# MCU.net
KiCad netlist of a schematic drawn in Altium Designer
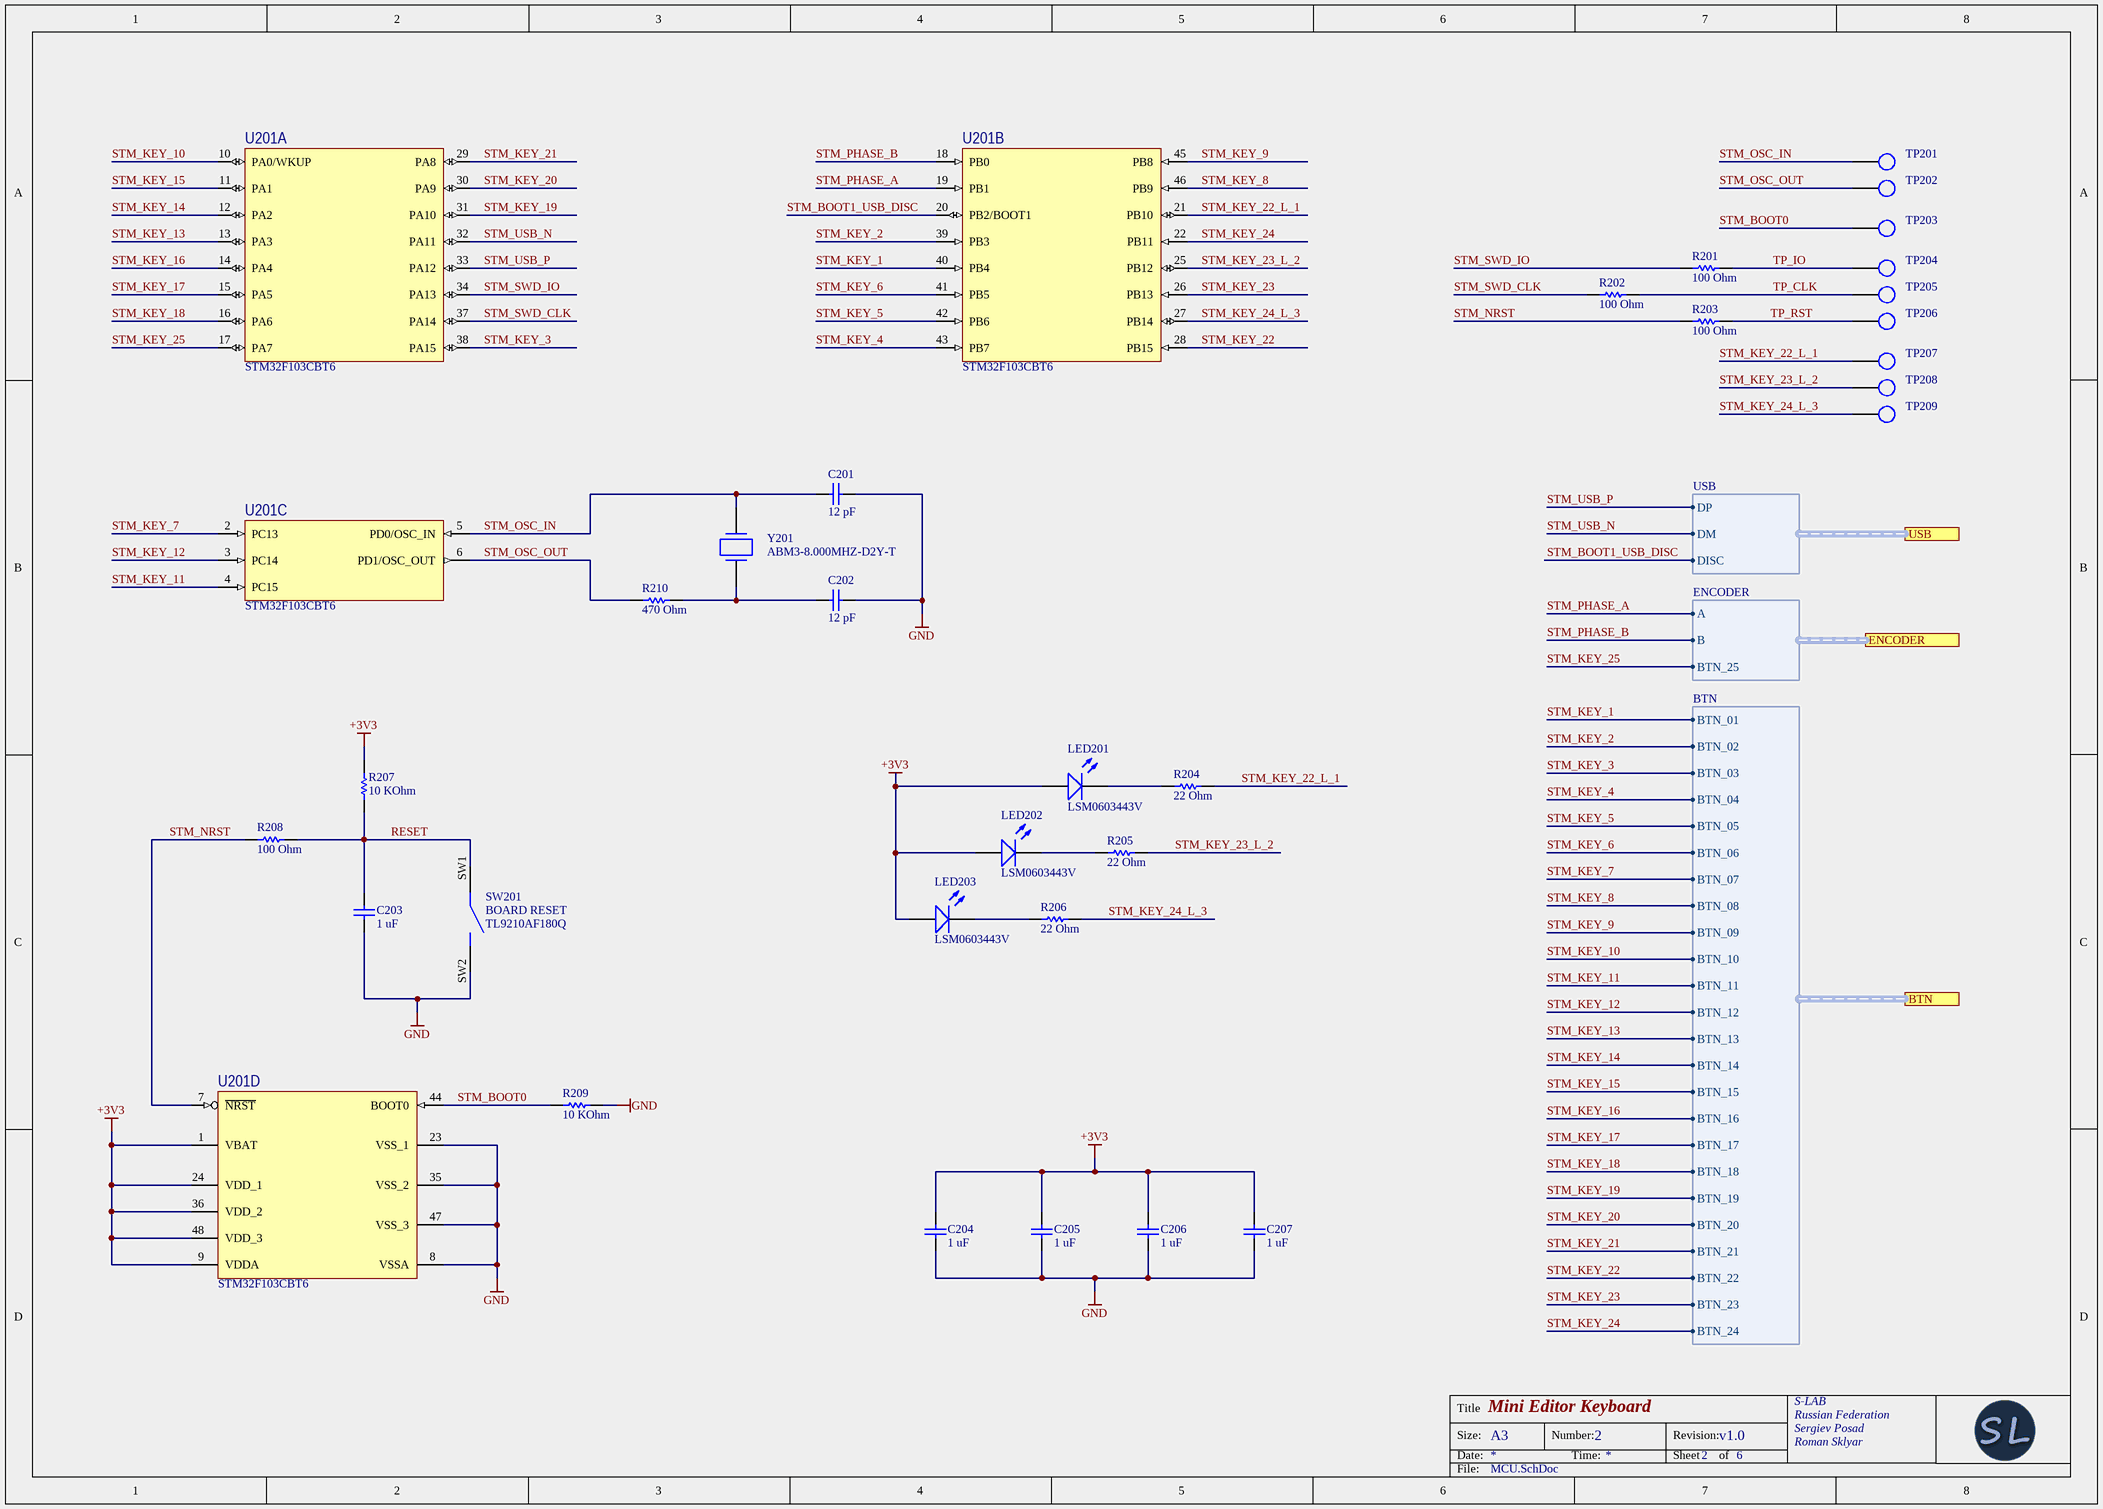
[diagram p0: MCU.SchDoc]

(export (version "E")
  (design (tool "Eeschema 10.0.6"))
  (components
    (comp (ref "C201")
      (value "CAP-12P")
      (footprint "CAPC0603")
      (description "Chip Capacitor, 12 pF, +/- 5%")
      (fields (field (name "TOLERANCE") "5 %") (field (name "CAPACITANCE") "12 pF"))
      (libsource (lib "Конденсаторы керамические SMD") (part "CAP-12P"))
    )
    (comp (ref "C202")
      (value "CAP-12P")
      (footprint "CAPC0603")
      (description "Chip Capacitor, 12 pF, +/- 5%")
      (fields (field (name "TOLERANCE") "5 %") (field (name "CAPACITANCE") "12 pF"))
      (libsource (lib "Конденсаторы керамические SMD") (part "CAP-12P"))
    )
    (comp (ref "C203")
      (value "CAP-1U")
      (footprint "CAPC0805")
      (description "Chip Capacitor, 1 uF, +/- 5%")
      (fields (field (name "TOLERANCE") "5 %") (field (name "CAPACITANCE") "1 uF"))
      (libsource (lib "Конденсаторы керамические SMD") (part "CAP-1U"))
    )
    (comp (ref "C204")
      (value "CAP-1U")
      (footprint "CAPC0805")
      (description "Chip Capacitor, 1 uF, +/- 5%")
      (fields (field (name "TOLERANCE") "5 %") (field (name "CAPACITANCE") "1 uF"))
      (libsource (lib "Конденсаторы керамические SMD") (part "CAP-1U"))
    )
    (comp (ref "C205")
      (value "CAP-1U")
      (footprint "CAPC0805")
      (description "Chip Capacitor, 1 uF, +/- 5%")
      (fields (field (name "TOLERANCE") "5 %") (field (name "CAPACITANCE") "1 uF"))
      (libsource (lib "Конденсаторы керамические SMD") (part "CAP-1U"))
    )
    (comp (ref "C206")
      (value "CAP-1U")
      (footprint "CAPC0805")
      (description "Chip Capacitor, 1 uF, +/- 5%")
      (fields (field (name "TOLERANCE") "5 %") (field (name "CAPACITANCE") "1 uF"))
      (libsource (lib "Конденсаторы керамические SMD") (part "CAP-1U"))
    )
    (comp (ref "C207")
      (value "CAP-1U")
      (footprint "CAPC0805")
      (description "Chip Capacitor, 1 uF, +/- 5%")
      (fields (field (name "TOLERANCE") "5 %") (field (name "CAPACITANCE") "1 uF"))
      (libsource (lib "Конденсаторы керамические SMD") (part "CAP-1U"))
    )
    (comp (ref "LED201")
      (value "LSM0603443V")
      (footprint "LSM0603-Series")
      (description "White LED 0603 3V 20mA")
      (fields (field (name "PARTNUMBER") "LSM0603443V"))
      (libsource (lib "Светодиоды") (part "LSM0603443V"))
    )
    (comp (ref "LED202")
      (value "LSM0603443V")
      (footprint "LSM0603-Series")
      (description "White LED 0603 3V 20mA")
      (fields (field (name "PARTNUMBER") "LSM0603443V"))
      (libsource (lib "Светодиоды") (part "LSM0603443V"))
    )
    (comp (ref "LED203")
      (value "LSM0603443V")
      (footprint "LSM0603-Series")
      (description "White LED 0603 3V 20mA")
      (fields (field (name "PARTNUMBER") "LSM0603443V"))
      (libsource (lib "Светодиоды") (part "LSM0603443V"))
    )
    (comp (ref "R201")
      (value "RES-100")
      (footprint "RES0603")
      (description "Chip Resistor, 100 Ohm, +/- 1%")
      (fields (field (name "TOLERANCE") "1 %") (field (name "RESISTANCE") "100 Ohm"))
      (libsource (lib "Резисторы SMD") (part "RES-100"))
    )
    (comp (ref "R202")
      (value "RES-100")
      (footprint "RES0603")
      (description "Chip Resistor, 100 Ohm, +/- 1%")
      (fields (field (name "TOLERANCE") "1 %") (field (name "RESISTANCE") "100 Ohm"))
      (libsource (lib "Резисторы SMD") (part "RES-100"))
    )
    (comp (ref "R203")
      (value "RES-100")
      (footprint "RES0603")
      (description "Chip Resistor, 100 Ohm, +/- 1%")
      (fields (field (name "TOLERANCE") "1 %") (field (name "RESISTANCE") "100 Ohm"))
      (libsource (lib "Резисторы SMD") (part "RES-100"))
    )
    (comp (ref "R204")
      (value "RES-22")
      (footprint "RES0603")
      (description "Chip Resistor, 22 Ohm, +/- 1%")
      (fields (field (name "TOLERANCE") "1 %") (field (name "RESISTANCE") "22 Ohm"))
      (libsource (lib "Резисторы SMD") (part "RES-22"))
    )
    (comp (ref "R205")
      (value "RES-22")
      (footprint "RES0603")
      (description "Chip Resistor, 22 Ohm, +/- 1%")
      (fields (field (name "TOLERANCE") "1 %") (field (name "RESISTANCE") "22 Ohm"))
      (libsource (lib "Резисторы SMD") (part "RES-22"))
    )
    (comp (ref "R206")
      (value "RES-22")
      (footprint "RES0603")
      (description "Chip Resistor, 22 Ohm, +/- 1%")
      (fields (field (name "TOLERANCE") "1 %") (field (name "RESISTANCE") "22 Ohm"))
      (libsource (lib "Резисторы SMD") (part "RES-22"))
    )
    (comp (ref "R207")
      (value "RES-10K")
      (footprint "RES0603")
      (description "Chip Resistor, 10 KOhm, +/- 1%")
      (fields (field (name "TOLERANCE") "1 %") (field (name "RESISTANCE") "10 KOhm"))
      (libsource (lib "Резисторы SMD") (part "RES-10K"))
    )
    (comp (ref "R208")
      (value "RES-100")
      (footprint "RES0603")
      (description "Chip Resistor, 100 Ohm, +/- 1%")
      (fields (field (name "TOLERANCE") "1 %") (field (name "RESISTANCE") "100 Ohm"))
      (libsource (lib "Резисторы SMD") (part "RES-100"))
    )
    (comp (ref "R209")
      (value "RES-10K")
      (footprint "RES0603")
      (description "Chip Resistor, 10 KOhm, +/- 1%")
      (fields (field (name "TOLERANCE") "1 %") (field (name "RESISTANCE") "10 KOhm"))
      (libsource (lib "Резисторы SMD") (part "RES-10K"))
    )
    (comp (ref "R210")
      (value "RES-470")
      (footprint "RES0603")
      (description "Chip Resistor, 470 Ohm, +/- 1%")
      (fields (field (name "TOLERANCE") "1 %") (field (name "RESISTANCE") "470 Ohm"))
      (libsource (lib "Резисторы SMD") (part "RES-470"))
    )
    (comp (ref "SW201")
      (value "BOARD RESET")
      (footprint "TL9210AF180Q")
      (description "SMD Tactile Switch, SPST, 180 gf, 12 VDC, 50 mA")
      (fields (field (name "MODEL") "TL9210AF180Q"))
      (libsource (lib "Кнопки") (part "TL9210AF180Q"))
    )
    (comp (ref "TP201") (value "~") (footprint "TP_C-0.5mm") (libsource (lib "Разъемы") (part "TestPad")))
    (comp (ref "TP202") (value "~") (footprint "TP_C-0.5mm") (libsource (lib "Разъемы") (part "TestPad")))
    (comp (ref "TP203") (value "~") (footprint "TP_C-0.5mm") (libsource (lib "Разъемы") (part "TestPad")))
    (comp (ref "TP204") (value "~") (footprint "TP_C-0.5mm") (libsource (lib "Разъемы") (part "TestPad")))
    (comp (ref "TP205") (value "~") (footprint "TP_C-0.5mm") (libsource (lib "Разъемы") (part "TestPad")))
    (comp (ref "TP206") (value "~") (footprint "TP_C-0.5mm") (libsource (lib "Разъемы") (part "TestPad")))
    (comp (ref "TP207") (value "~") (footprint "TP_C-0.5mm") (libsource (lib "Разъемы") (part "TestPad")))
    (comp (ref "TP208") (value "~") (footprint "TP_C-0.5mm") (libsource (lib "Разъемы") (part "TestPad")))
    (comp (ref "TP209") (value "~") (footprint "TP_C-0.5mm") (libsource (lib "Разъемы") (part "TestPad")))
    (comp (ref "U201")
      (value "STM32F103CBT6")
      (footprint "LQFP-48-STM32")
      (description "ARM based 32-bit MCU with 64 or 128 KB Flash")
      (fields (field (name "PARTNUMBER") "STM32F103CBT6"))
      (libsource (lib "Микроконтроллеры") (part "STM32F103C8T6"))
    )
    (comp (ref "Y201")
      (value "ABM3-8.000MHZ-D2Y-T")
      (footprint "ABM3-2P")
      (description "8MHz ±20ppm 18pF 140 Ohm SMD Crystal Resonators")
      (fields (field (name "PARTNUMBER") "ABM3-8.000MHZ-D2Y-T"))
      (libsource (lib "Кврцы") (part "ABM3-8.000MHZ-D2Y-T"))
    )
  )
  (nets
    (net (code "4") (name "+3V3") (class "Default")
      (node (ref "C204") (pin "2") (pinfunction "2_2") (pintype "passive"))
      (node (ref "C205") (pin "2") (pinfunction "2_2") (pintype "passive"))
      (node (ref "C206") (pin "2") (pinfunction "2_2") (pintype "passive"))
      (node (ref "C207") (pin "2") (pinfunction "2_2") (pintype "passive"))
      (node (ref "LED201") (pin "2") (pinfunction "A_2") (pintype "passive"))
      (node (ref "LED202") (pin "2") (pinfunction "A_2") (pintype "passive"))
      (node (ref "LED203") (pin "2") (pinfunction "A_2") (pintype "passive"))
      (node (ref "R207") (pin "2") (pinfunction "2_2") (pintype "passive"))
      (node (ref "U201") (pin "1") (pinfunction "VBAT_1") (pintype "power_in"))
      (node (ref "U201") (pin "24") (pinfunction "VDD_1_24") (pintype "power_in"))
      (node (ref "U201") (pin "36") (pinfunction "VDD_2_36") (pintype "power_in"))
      (node (ref "U201") (pin "48") (pinfunction "VDD_3_48") (pintype "power_in"))
      (node (ref "U201") (pin "9") (pinfunction "VDDA_9") (pintype "power_in"))
    )
    (net (code "5") (name "/RESET") (class "Default")
      (node (ref "C203") (pin "1") (pinfunction "1_1") (pintype "passive"))
      (node (ref "R207") (pin "1") (pinfunction "1_1") (pintype "passive"))
      (node (ref "R208") (pin "2") (pinfunction "2_2") (pintype "passive"))
      (node (ref "SW201") (pin "SW1") (pintype "passive"))
    )
    (net (code "6") (name "/STM_BOOT0") (class "Default")
      (node (ref "R209") (pin "1") (pinfunction "1_1") (pintype "passive"))
      (node (ref "TP203") (pin "1") (pintype "passive"))
      (node (ref "U201") (pin "44") (pinfunction "BOOT0_44") (pintype "input"))
    )
    (net (code "7") (name "/STM_BOOT1_USB_DISC") (class "Default")
      (node (ref "U201") (pin "20") (pinfunction "PB2_20") (pintype "bidirectional"))
    )
    (net (code "8") (name "/STM_KEY_1") (class "Default")
      (node (ref "U201") (pin "40") (pinfunction "PB4_40") (pintype "bidirectional"))
    )
    (net (code "9") (name "/STM_KEY_2") (class "Default")
      (node (ref "U201") (pin "39") (pinfunction "PB3_39") (pintype "bidirectional"))
    )
    (net (code "10") (name "/STM_KEY_3") (class "Default")
      (node (ref "U201") (pin "38") (pinfunction "PA15_38") (pintype "bidirectional"))
    )
    (net (code "11") (name "/STM_KEY_4") (class "Default")
      (node (ref "U201") (pin "43") (pinfunction "PB7_43") (pintype "bidirectional"))
    )
    (net (code "12") (name "/STM_KEY_5") (class "Default")
      (node (ref "U201") (pin "42") (pinfunction "PB6_42") (pintype "bidirectional"))
    )
    (net (code "13") (name "/STM_KEY_6") (class "Default")
      (node (ref "U201") (pin "41") (pinfunction "PB5_41") (pintype "bidirectional"))
    )
    (net (code "14") (name "/STM_KEY_7") (class "Default")
      (node (ref "U201") (pin "2") (pinfunction "PC13/TAMPER-RTC_2") (pintype "bidirectional"))
    )
    (net (code "15") (name "/STM_KEY_8") (class "Default")
      (node (ref "U201") (pin "46") (pinfunction "PB9_46") (pintype "bidirectional"))
    )
    (net (code "16") (name "/STM_KEY_9") (class "Default")
      (node (ref "U201") (pin "45") (pinfunction "PB8_45") (pintype "bidirectional"))
    )
    (net (code "17") (name "/STM_KEY_10") (class "Default")
      (node (ref "U201") (pin "10") (pinfunction "PA0/WKUP_10") (pintype "bidirectional"))
    )
    (net (code "18") (name "/STM_KEY_11") (class "Default")
      (node (ref "U201") (pin "4") (pinfunction "PC15/OSC32_OUT_4") (pintype "bidirectional"))
    )
    (net (code "19") (name "/STM_KEY_12") (class "Default")
      (node (ref "U201") (pin "3") (pinfunction "PC14/OSC32_IN_3") (pintype "bidirectional"))
    )
    (net (code "20") (name "/STM_KEY_13") (class "Default")
      (node (ref "U201") (pin "13") (pinfunction "PA3_13") (pintype "bidirectional"))
    )
    (net (code "21") (name "/STM_KEY_14") (class "Default")
      (node (ref "U201") (pin "12") (pinfunction "PA2_12") (pintype "bidirectional"))
    )
    (net (code "22") (name "/STM_KEY_15") (class "Default")
      (node (ref "U201") (pin "11") (pinfunction "PA1_11") (pintype "bidirectional"))
    )
    (net (code "23") (name "/STM_KEY_16") (class "Default")
      (node (ref "U201") (pin "14") (pinfunction "PA4_14") (pintype "bidirectional"))
    )
    (net (code "24") (name "/STM_KEY_17") (class "Default")
      (node (ref "U201") (pin "15") (pinfunction "PA5_15") (pintype "bidirectional"))
    )
    (net (code "25") (name "/STM_KEY_18") (class "Default")
      (node (ref "U201") (pin "16") (pinfunction "PA6_16") (pintype "bidirectional"))
    )
    (net (code "26") (name "/STM_KEY_19") (class "Default")
      (node (ref "U201") (pin "31") (pinfunction "PA10_31") (pintype "bidirectional"))
    )
    (net (code "27") (name "/STM_KEY_20") (class "Default")
      (node (ref "U201") (pin "30") (pinfunction "PA9_30") (pintype "bidirectional"))
    )
    (net (code "28") (name "/STM_KEY_21") (class "Default")
      (node (ref "U201") (pin "29") (pinfunction "PA8_29") (pintype "bidirectional"))
    )
    (net (code "29") (name "/STM_KEY_22") (class "Default")
      (node (ref "U201") (pin "28") (pinfunction "PB15_28") (pintype "bidirectional"))
    )
    (net (code "30") (name "/STM_KEY_22_L_1") (class "Default")
      (node (ref "R204") (pin "2") (pinfunction "2_2") (pintype "passive"))
      (node (ref "TP207") (pin "1") (pintype "passive"))
      (node (ref "U201") (pin "21") (pinfunction "PB10_21") (pintype "bidirectional"))
    )
    (net (code "31") (name "/STM_KEY_23") (class "Default")
      (node (ref "U201") (pin "26") (pinfunction "PB13_26") (pintype "bidirectional"))
    )
    (net (code "32") (name "/STM_KEY_23_L_2") (class "Default")
      (node (ref "R205") (pin "2") (pinfunction "2_2") (pintype "passive"))
      (node (ref "TP208") (pin "1") (pintype "passive"))
      (node (ref "U201") (pin "25") (pinfunction "PB12_25") (pintype "bidirectional"))
    )
    (net (code "33") (name "/STM_KEY_24") (class "Default")
      (node (ref "U201") (pin "22") (pinfunction "PB11_22") (pintype "bidirectional"))
    )
    (net (code "34") (name "/STM_KEY_24_L_3") (class "Default")
      (node (ref "R206") (pin "2") (pinfunction "2_2") (pintype "passive"))
      (node (ref "TP209") (pin "1") (pintype "passive"))
      (node (ref "U201") (pin "27") (pinfunction "PB14_27") (pintype "bidirectional"))
    )
    (net (code "35") (name "/STM_KEY_25") (class "Default")
      (node (ref "U201") (pin "17") (pinfunction "PA7_17") (pintype "bidirectional"))
    )
    (net (code "36") (name "/STM_NRST") (class "Default")
      (node (ref "R203") (pin "1") (pinfunction "1_1") (pintype "passive"))
      (node (ref "R208") (pin "1") (pinfunction "1_1") (pintype "passive"))
      (node (ref "U201") (pin "7") (pinfunction "~{NRST}_7") (pintype "input"))
    )
    (net (code "37") (name "/STM_OSC_IN") (class "Default")
      (node (ref "C201") (pin "2") (pinfunction "2_2") (pintype "passive"))
      (node (ref "TP201") (pin "1") (pintype "passive"))
      (node (ref "U201") (pin "5") (pinfunction "PD0/OSC_IN_5") (pintype "bidirectional"))
      (node (ref "Y201") (pin "2") (pinfunction "OSC2_2") (pintype "passive"))
    )
    (net (code "38") (name "/STM_OSC_OUT") (class "Default")
      (node (ref "R210") (pin "1") (pinfunction "1_1") (pintype "passive"))
      (node (ref "TP202") (pin "1") (pintype "passive"))
      (node (ref "U201") (pin "6") (pinfunction "PD1/OSC_OUT_6") (pintype "bidirectional"))
    )
    (net (code "39") (name "/STM_PHASE_A") (class "Default")
      (node (ref "U201") (pin "19") (pinfunction "PB1_19") (pintype "bidirectional"))
    )
    (net (code "40") (name "/STM_PHASE_B") (class "Default")
      (node (ref "U201") (pin "18") (pinfunction "PB0_18") (pintype "bidirectional"))
    )
    (net (code "41") (name "/STM_SWD_CLK") (class "Default")
      (node (ref "R202") (pin "1") (pinfunction "1_1") (pintype "passive"))
      (node (ref "U201") (pin "37") (pinfunction "PA14_37") (pintype "bidirectional"))
    )
    (net (code "42") (name "/STM_SWD_IO") (class "Default")
      (node (ref "R201") (pin "1") (pinfunction "1_1") (pintype "passive"))
      (node (ref "U201") (pin "34") (pinfunction "PA13_34") (pintype "bidirectional"))
    )
    (net (code "43") (name "/STM_USB_N") (class "Default")
      (node (ref "U201") (pin "32") (pinfunction "PA11_32") (pintype "bidirectional"))
    )
    (net (code "44") (name "/STM_USB_P") (class "Default")
      (node (ref "U201") (pin "33") (pinfunction "PA12_33") (pintype "bidirectional"))
    )
    (net (code "45") (name "/TP_CLK") (class "Default")
      (node (ref "R202") (pin "2") (pinfunction "2_2") (pintype "passive"))
      (node (ref "TP205") (pin "1") (pintype "passive"))
    )
    (net (code "46") (name "/TP_IO") (class "Default")
      (node (ref "R201") (pin "2") (pinfunction "2_2") (pintype "passive"))
      (node (ref "TP204") (pin "1") (pintype "passive"))
    )
    (net (code "47") (name "/TP_RST") (class "Default")
      (node (ref "R203") (pin "2") (pinfunction "2_2") (pintype "passive"))
      (node (ref "TP206") (pin "1") (pintype "passive"))
    )
    (net (code "51") (name "GND") (class "Default")
      (node (ref "C201") (pin "1") (pinfunction "1_1") (pintype "passive"))
      (node (ref "C202") (pin "1") (pinfunction "1_1") (pintype "passive"))
      (node (ref "C203") (pin "2") (pinfunction "2_2") (pintype "passive"))
      (node (ref "C204") (pin "1") (pinfunction "1_1") (pintype "passive"))
      (node (ref "C205") (pin "1") (pinfunction "1_1") (pintype "passive"))
      (node (ref "C206") (pin "1") (pinfunction "1_1") (pintype "passive"))
      (node (ref "C207") (pin "1") (pinfunction "1_1") (pintype "passive"))
      (node (ref "R209") (pin "2") (pinfunction "2_2") (pintype "passive"))
      (node (ref "SW201") (pin "SW2") (pintype "passive"))
      (node (ref "U201") (pin "23") (pinfunction "VSS_1_23") (pintype "power_in"))
      (node (ref "U201") (pin "35") (pinfunction "VSS_2_35") (pintype "power_in"))
      (node (ref "U201") (pin "47") (pinfunction "VSS_3_47") (pintype "power_in"))
      (node (ref "U201") (pin "8") (pinfunction "VSSA_8") (pintype "power_in"))
    )
    (net (code "52") (name "Net-(LED201-K)") (class "Default")
      (node (ref "LED201") (pin "1") (pinfunction "K_1") (pintype "passive"))
      (node (ref "R204") (pin "1") (pinfunction "1_1") (pintype "passive"))
    )
    (net (code "53") (name "Net-(LED202-K)") (class "Default")
      (node (ref "LED202") (pin "1") (pinfunction "K_1") (pintype "passive"))
      (node (ref "R205") (pin "1") (pinfunction "1_1") (pintype "passive"))
    )
    (net (code "54") (name "Net-(LED203-K)") (class "Default")
      (node (ref "LED203") (pin "1") (pinfunction "K_1") (pintype "passive"))
      (node (ref "R206") (pin "1") (pinfunction "1_1") (pintype "passive"))
    )
    (net (code "55") (name "Net-(Y201-OSC1)") (class "Default")
      (node (ref "C202") (pin "2") (pinfunction "2_2") (pintype "passive"))
      (node (ref "R210") (pin "2") (pinfunction "2_2") (pintype "passive"))
      (node (ref "Y201") (pin "1") (pinfunction "OSC1_1") (pintype "passive"))
    )
  )
)
